# 4G_Module.net
KiCad netlist of a schematic drawn in Altium Designer
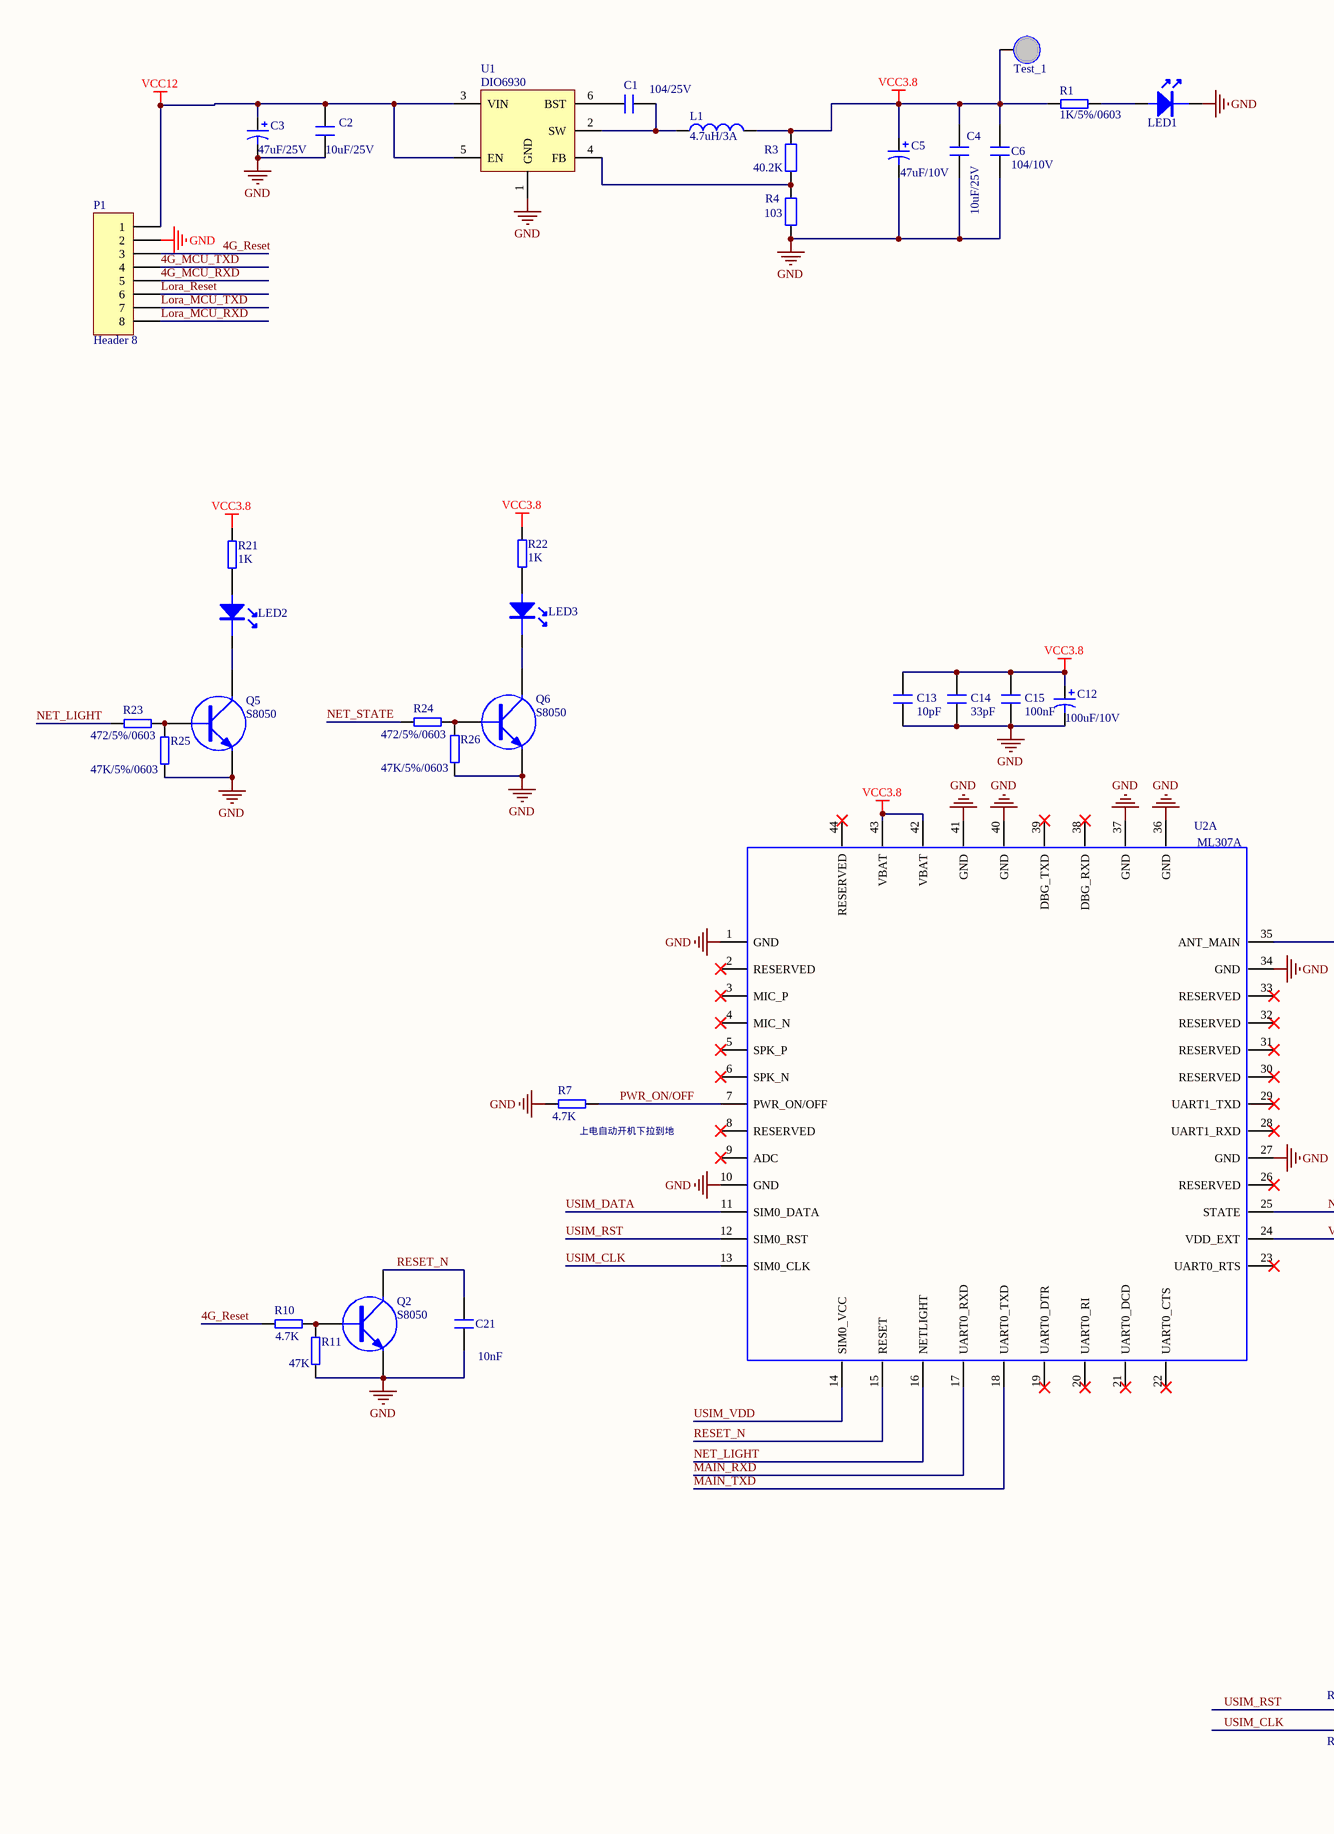
[diagram p0: 4G_Module.SchDoc, left]
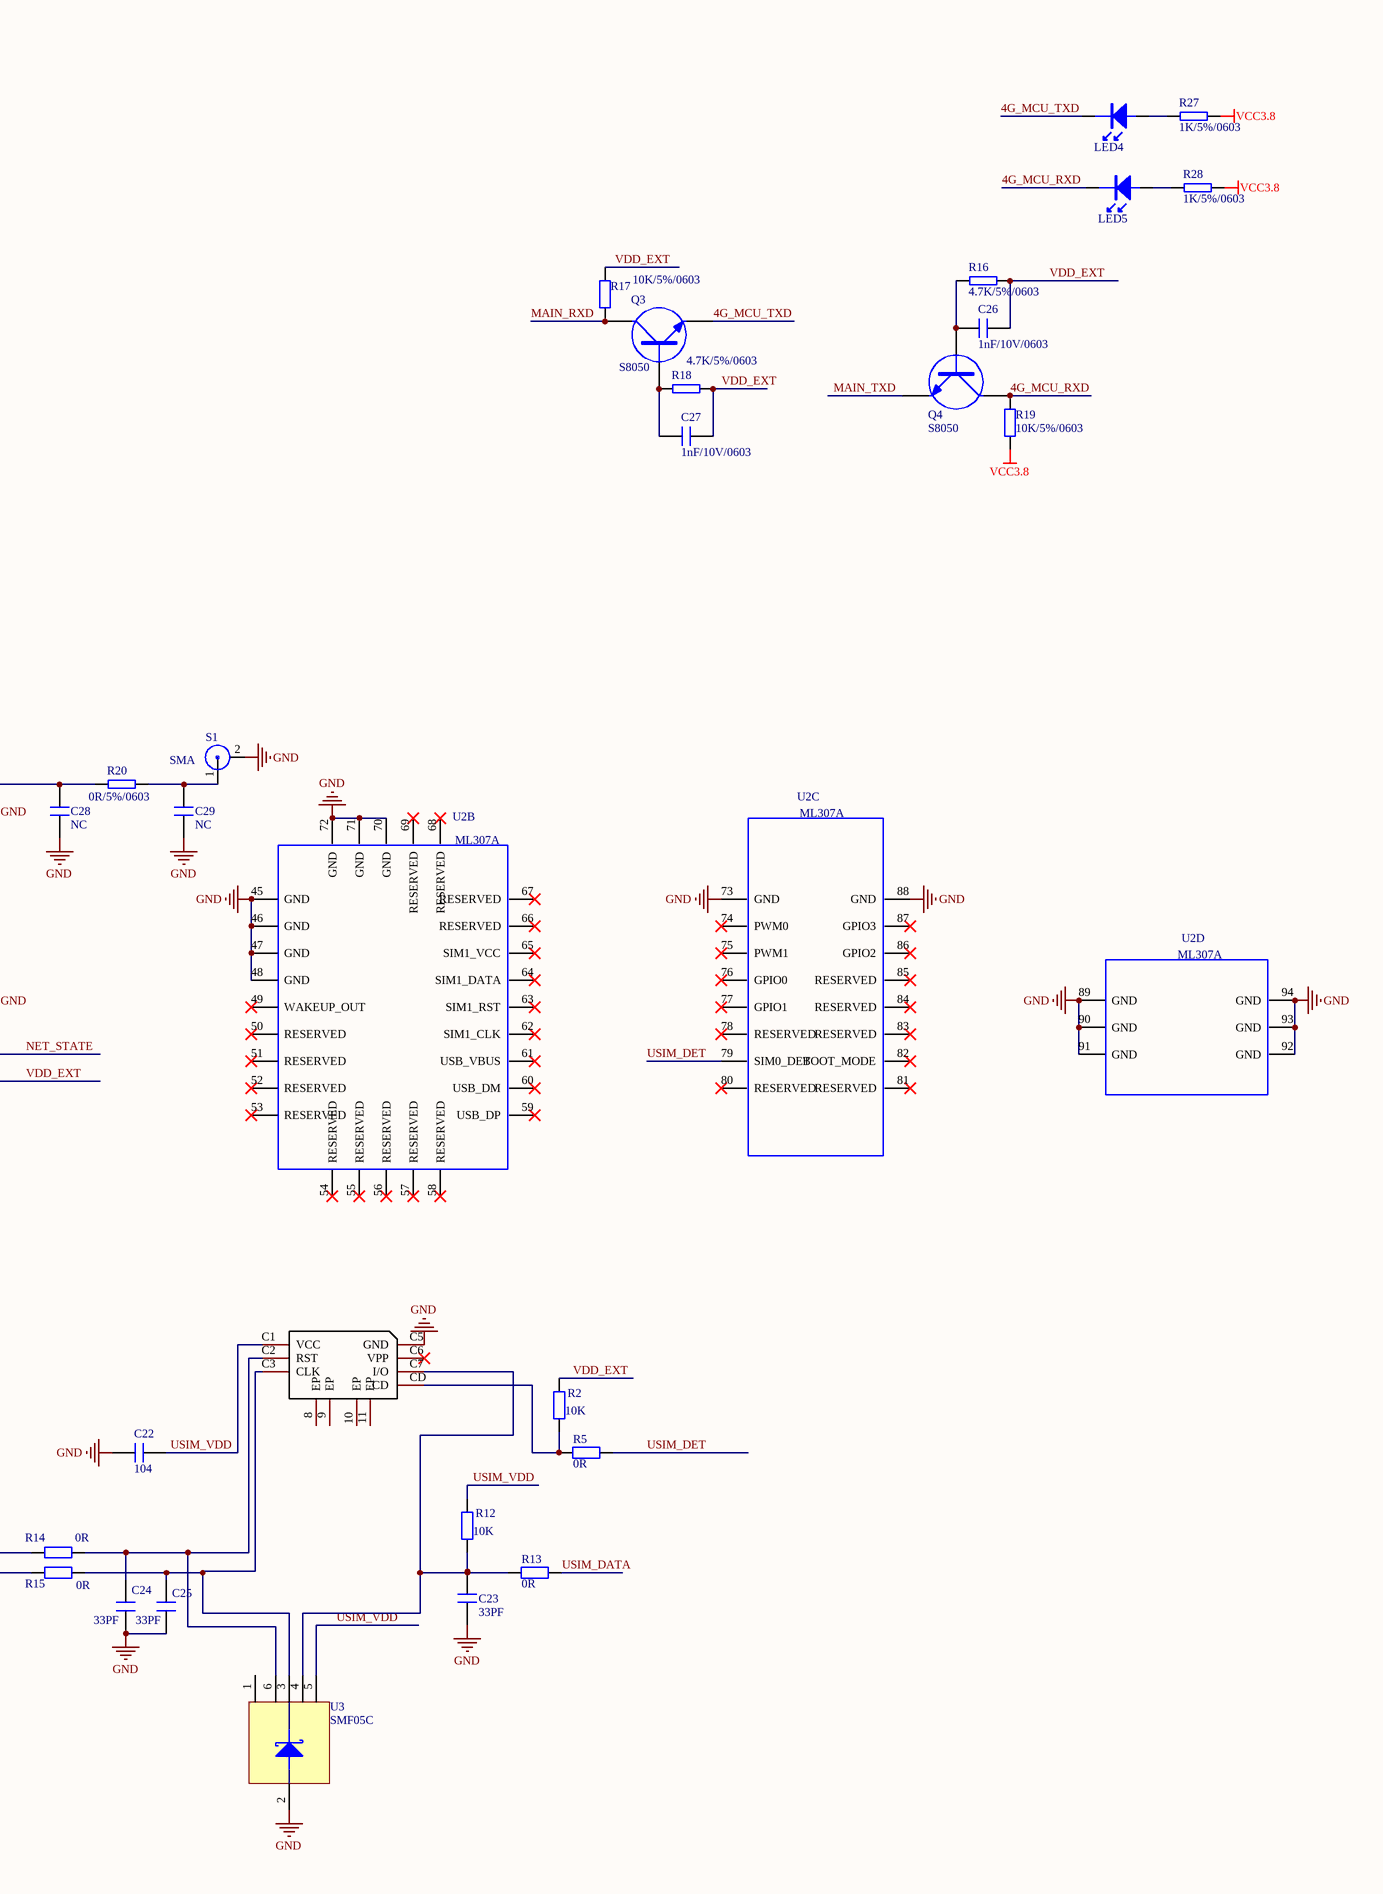
[diagram p1: 4G_Module.SchDoc, right]

(export (version "E")
  (design (tool "Eeschema 10.0.6"))
  (components
    (comp (ref "C1") (value "104/25V") (footprint "0603R") (libsource (lib "ES_Schematic") (part "CAP_1")))
    (comp (ref "C2") (value "10uF/25V") (footprint "0603R") (libsource (lib "ES_Schematic") (part "CAP")))
    (comp (ref "C3")
      (value "47uF/25V")
      (footprint "0805R")
      (description "Polarized Capacitor (Radial)")
      (fields (field (name "PUBLISHER") "Altium Limited"))
      (libsource (lib "Miscellaneous Devices") (part "Cap Pol1"))
    )
    (comp (ref "C4") (value "10uF/25V") (footprint "0603R") (libsource (lib "ES_Schematic") (part "CAP")))
    (comp (ref "C5")
      (value "47uF/10V")
      (footprint "0805R")
      (description "Polarized Capacitor (Radial)")
      (fields (field (name "PUBLISHER") "Altium Limited"))
      (libsource (lib "Miscellaneous Devices") (part "Cap Pol1"))
    )
    (comp (ref "C6") (value "104/10V") (footprint "0603R") (libsource (lib "ES_Schematic") (part "CAP_1")))
    (comp (ref "C12")
      (value "100uF/10V")
      (footprint "C1210")
      (description "Polarized Capacitor (Radial)")
      (fields (field (name "PUBLISHER") "Altium Limited"))
      (libsource (lib "Miscellaneous Devices") (part "Cap Pol1"))
    )
    (comp (ref "C13") (value "10pF") (footprint "0603R") (libsource (lib "ES_Schematic") (part "CAP_1")))
    (comp (ref "C14") (value "33pF") (footprint "0603R") (libsource (lib "ES_Schematic") (part "CAP_1")))
    (comp (ref "C15") (value "100nF") (footprint "0603R") (libsource (lib "ES_Schematic") (part "CAP_1")))
    (comp (ref "C21") (value "10nF") (footprint "0603R") (libsource (lib "ES_Schematic") (part "CAP_1")))
    (comp (ref "C22") (value "104") (footprint "0603R") (libsource (lib "ES_Schematic") (part "CAP")))
    (comp (ref "C23") (value "33PF") (footprint "0603R") (libsource (lib "ES_Schematic") (part "CAP")))
    (comp (ref "C24") (value "33PF") (footprint "0603R") (libsource (lib "ES_Schematic") (part "CAP")))
    (comp (ref "C25") (value "33PF") (footprint "0603R") (libsource (lib "ES_Schematic") (part "CAP")))
    (comp (ref "C26")
      (value "1nF/10V/0603")
      (footprint "0603R")
      (libsource (lib "ES_Schematic") (part "CAP"))
    )
    (comp (ref "C27")
      (value "1nF/10V/0603")
      (footprint "0603R")
      (libsource (lib "ES_Schematic") (part "CAP"))
    )
    (comp (ref "C28") (value "NC") (footprint "0603R") (libsource (lib "ES_Schematic") (part "CAP")))
    (comp (ref "C29") (value "NC") (footprint "0603R") (libsource (lib "ES_Schematic") (part "CAP")))
    (comp (ref "CARD1")
      (value "SMN-303")
      (footprint "Nano-SIM")
      (fields (field (name "MANUFACTURER") "XUNPU(讯普)"))
      (libsource (lib "altium-import") (part "root_0_SMN-303_"))
    )
    (comp (ref "L1")
      (value "4.7uH/3A")
      (footprint "CD54")
      (description "Inductor")
      (fields (field (name "PUBLISHER") "Altium Limited"))
      (libsource (lib "Miscellaneous Devices") (part "Inductor"))
    )
    (comp (ref "LED1") (value "LED") (footprint "0603LED") (libsource (lib "ES_Schematic") (part "LED")))
    (comp (ref "LED2") (value "LED") (footprint "0603LED") (libsource (lib "ES_Schematic") (part "LED")))
    (comp (ref "LED3") (value "LED") (footprint "0603LED") (libsource (lib "ES_Schematic") (part "LED")))
    (comp (ref "LED4") (value "LED") (footprint "0603LED") (libsource (lib "ES_Schematic") (part "LED")))
    (comp (ref "LED5") (value "LED") (footprint "0603LED") (libsource (lib "ES_Schematic") (part "LED")))
    (comp (ref "P1")
      (value "Header 8")
      (footprint "HDR1X8")
      (description "Header, 8-Pin")
      (fields (field (name "PUBLISHER") "Altium Limited"))
      (libsource (lib "Miscellaneous Connectors") (part "Header 8"))
    )
    (comp (ref "Q2") (value "S8050") (footprint "SOT-23") (libsource (lib "ES_Schematic") (part "NPN")))
    (comp (ref "Q3") (value "S8050") (footprint "SOT-23") (libsource (lib "ES_Schematic") (part "NPN")))
    (comp (ref "Q4") (value "S8050") (footprint "SOT-23") (libsource (lib "ES_Schematic") (part "NPN")))
    (comp (ref "Q5") (value "S8050") (footprint "SOT-23") (libsource (lib "ES_Schematic") (part "NPN")))
    (comp (ref "Q6") (value "S8050") (footprint "SOT-23") (libsource (lib "ES_Schematic") (part "NPN")))
    (comp (ref "R1") (value "1K/5%/0603") (footprint "0603R") (libsource (lib "ES_Schematic") (part "RES")))
    (comp (ref "R2")
      (value "10K")
      (footprint "0603R")
      (description "Resistor")
      (fields (field (name "PUBLISHER") "Altium Limited"))
      (libsource (lib "Miscellaneous Devices") (part "Res2"))
    )
    (comp (ref "R3")
      (value "40.2K")
      (footprint "0603R")
      (description "Resistor")
      (fields (field (name "PUBLISHER") "Altium Limited"))
      (libsource (lib "Miscellaneous Devices") (part "Res2"))
    )
    (comp (ref "R4")
      (value "103")
      (footprint "0603R")
      (description "Resistor")
      (fields (field (name "PUBLISHER") "Altium Limited"))
      (libsource (lib "Miscellaneous Devices") (part "Res2"))
    )
    (comp (ref "R5")
      (value "0R")
      (footprint "0603R")
      (description "Resistor")
      (fields (field (name "PUBLISHER") "Altium Limited"))
      (libsource (lib "") (part "Res2_1"))
    )
    (comp (ref "R7") (value "4.7K") (footprint "0603R") (libsource (lib "ES_Schematic") (part "RES")))
    (comp (ref "R10") (value "4.7K") (footprint "0603R") (libsource (lib "ES_Schematic") (part "RES")))
    (comp (ref "R11") (value "47K") (footprint "0603R") (libsource (lib "ES_Schematic") (part "RES")))
    (comp (ref "R12")
      (value "10K")
      (footprint "0603R")
      (description "Resistor")
      (fields (field (name "PUBLISHER") "Altium Limited"))
      (libsource (lib "Miscellaneous Devices") (part "Res2"))
    )
    (comp (ref "R13")
      (value "0R")
      (footprint "0603R")
      (description "Resistor")
      (fields (field (name "PUBLISHER") "Altium Limited"))
      (libsource (lib "") (part "Res2_1"))
    )
    (comp (ref "R14")
      (value "0R")
      (footprint "0603R")
      (description "Resistor")
      (fields (field (name "PUBLISHER") "Altium Limited"))
      (libsource (lib "") (part "Res2_1"))
    )
    (comp (ref "R15")
      (value "0R")
      (footprint "0603R")
      (description "Resistor")
      (fields (field (name "PUBLISHER") "Altium Limited"))
      (libsource (lib "") (part "Res2_1"))
    )
    (comp (ref "R16")
      (value "4.7K/5%/0603")
      (footprint "0603R")
      (libsource (lib "ES_Schematic") (part "RES"))
    )
    (comp (ref "R17")
      (value "10K/5%/0603")
      (footprint "0603R")
      (description "Resistor")
      (fields (field (name "PUBLISHER") "Altium Limited"))
      (libsource (lib "Miscellaneous Devices") (part "Res2"))
    )
    (comp (ref "R18")
      (value "4.7K/5%/0603")
      (footprint "0603R")
      (libsource (lib "ES_Schematic") (part "RES"))
    )
    (comp (ref "R19")
      (value "10K/5%/0603")
      (footprint "0603R")
      (description "Resistor")
      (fields (field (name "PUBLISHER") "Altium Limited"))
      (libsource (lib "Miscellaneous Devices") (part "Res2"))
    )
    (comp (ref "R20") (value "0R/5%/0603") (footprint "0603R") (libsource (lib "ES_Schematic") (part "RES")))
    (comp (ref "R21") (value "1K") (footprint "0603R") (libsource (lib "ES_Schematic") (part "RES")))
    (comp (ref "R22") (value "1K") (footprint "0603R") (libsource (lib "ES_Schematic") (part "RES")))
    (comp (ref "R23") (value "472/5%/0603") (footprint "0603R") (libsource (lib "ES_Schematic") (part "RES")))
    (comp (ref "R24") (value "472/5%/0603") (footprint "0603R") (libsource (lib "ES_Schematic") (part "RES")))
    (comp (ref "R25") (value "47K/5%/0603") (footprint "0603R") (libsource (lib "ES_Schematic") (part "RES")))
    (comp (ref "R26") (value "47K/5%/0603") (footprint "0603R") (libsource (lib "ES_Schematic") (part "RES")))
    (comp (ref "R27") (value "1K/5%/0603") (footprint "0603R") (libsource (lib "ES_Schematic") (part "RES")))
    (comp (ref "R28") (value "1K/5%/0603") (footprint "0603R") (libsource (lib "ES_Schematic") (part "RES")))
    (comp (ref "S1") (value "SMA") (footprint "RF1-00283天线座") (libsource (lib "ES_Schematic") (part "SMA")))
    (comp (ref "Test_1") (value "MARK") (footprint "MARK") (libsource (lib "others") (part "MARK")))
    (comp (ref "U1")
      (value "DIO6930")
      (footprint "SOT-23-6DBV")
      (libsource (lib "ES_Schematic") (part "BL8032"))
    )
    (comp (ref "U2") (value "ML307A") (footprint "ML307A") (libsource (lib "") (part "ML307A_3")))
    (comp (ref "U3") (value "SMF05C") (footprint "SC70-6L") (libsource (lib "ES_Schematic") (part "SMF05C")))
  )
  (nets
    (net (code "1") (name "/4G_MCU_RXD") (class "Default")
      (node (ref "LED5") (pin "2") (pinfunction "2_2") (pintype "passive"))
      (node (ref "P1") (pin "5") (pinfunction "5_5") (pintype "passive"))
      (node (ref "Q4") (pin "3") (pinfunction "C_3") (pintype "passive"))
      (node (ref "R19") (pin "1") (pinfunction "1_1") (pintype "passive"))
    )
    (net (code "2") (name "/4G_MCU_TXD") (class "Default")
      (node (ref "LED4") (pin "2") (pinfunction "2_2") (pintype "passive"))
      (node (ref "P1") (pin "4") (pinfunction "4_4") (pintype "passive"))
      (node (ref "Q3") (pin "2") (pinfunction "E_2") (pintype "passive"))
    )
    (net (code "3") (name "/4G_Reset") (class "Default")
      (node (ref "P1") (pin "3") (pinfunction "3_3") (pintype "passive"))
      (node (ref "R10") (pin "1") (pinfunction "1_1") (pintype "passive"))
    )
    (net (code "4") (name "/Lora_MCU_RXD") (class "Default")
      (node (ref "P1") (pin "8") (pinfunction "8_8") (pintype "passive"))
    )
    (net (code "5") (name "/Lora_MCU_TXD") (class "Default")
      (node (ref "P1") (pin "7") (pinfunction "7_7") (pintype "passive"))
    )
    (net (code "6") (name "/Lora_Reset") (class "Default")
      (node (ref "P1") (pin "6") (pinfunction "6_6") (pintype "passive"))
    )
    (net (code "7") (name "/MAIN_RXD") (class "Default")
      (node (ref "Q3") (pin "3") (pinfunction "C_3") (pintype "passive"))
      (node (ref "R17") (pin "2") (pinfunction "2_2") (pintype "passive"))
      (node (ref "U2") (pin "17") (pinfunction "UART0_RXD_17") (pintype "passive"))
    )
    (net (code "8") (name "/MAIN_TXD") (class "Default")
      (node (ref "Q4") (pin "2") (pinfunction "E_2") (pintype "passive"))
      (node (ref "U2") (pin "18") (pinfunction "UART0_TXD_18") (pintype "passive"))
    )
    (net (code "9") (name "/NET_LIGHT") (class "Default")
      (node (ref "R23") (pin "1") (pinfunction "1_1") (pintype "passive"))
      (node (ref "U2") (pin "16") (pinfunction "NETLIGHT_16") (pintype "passive"))
    )
    (net (code "10") (name "/NET_STATE") (class "Default")
      (node (ref "R24") (pin "1") (pinfunction "1_1") (pintype "passive"))
      (node (ref "U2") (pin "25") (pinfunction "STATE_25") (pintype "passive"))
    )
    (net (code "11") (name "/PWR_ON{slash}OFF") (class "Default")
      (node (ref "R7") (pin "1") (pinfunction "1_1") (pintype "passive"))
      (node (ref "U2") (pin "7") (pinfunction "PWR_ON/OFF_7") (pintype "passive"))
    )
    (net (code "12") (name "/RESET_N") (class "Default")
      (node (ref "C21") (pin "2") (pinfunction "2_2") (pintype "passive"))
      (node (ref "Q2") (pin "3") (pinfunction "C_3") (pintype "passive"))
      (node (ref "U2") (pin "15") (pinfunction "RESET_15") (pintype "passive"))
    )
    (net (code "13") (name "/USIM_CLK") (class "Default")
      (node (ref "R15") (pin "2") (pinfunction "2_2") (pintype "passive"))
      (node (ref "U2") (pin "13") (pinfunction "SIM0_CLK_13") (pintype "passive"))
    )
    (net (code "14") (name "/USIM_DATA") (class "Default")
      (node (ref "R13") (pin "1") (pinfunction "1_1") (pintype "passive"))
      (node (ref "U2") (pin "11") (pinfunction "SIM0_DATA_11") (pintype "passive"))
    )
    (net (code "15") (name "/USIM_DET") (class "Default")
      (node (ref "R5") (pin "1") (pinfunction "1_1") (pintype "passive"))
      (node (ref "U2") (pin "79") (pinfunction "SIM0_DET_79") (pintype "passive"))
    )
    (net (code "16") (name "/USIM_RST") (class "Default")
      (node (ref "R14") (pin "2") (pinfunction "2_2") (pintype "passive"))
      (node (ref "U2") (pin "12") (pinfunction "SIM0_RST_12") (pintype "passive"))
    )
    (net (code "17") (name "/USIM_VDD") (class "Default")
      (node (ref "C22") (pin "2") (pinfunction "2_2") (pintype "passive"))
      (node (ref "CARD1") (pin "C1") (pinfunction "VCC_C1") (pintype "passive"))
      (node (ref "R12") (pin "1") (pinfunction "1_1") (pintype "passive"))
      (node (ref "U2") (pin "14") (pinfunction "SIM0_VCC_14") (pintype "passive"))
      (node (ref "U3") (pin "5") (pintype "passive"))
    )
    (net (code "18") (name "/VDD_EXT") (class "Default")
      (node (ref "C26") (pin "2") (pinfunction "2_2") (pintype "passive"))
      (node (ref "C27") (pin "2") (pinfunction "2_2") (pintype "passive"))
      (node (ref "R16") (pin "2") (pinfunction "2_2") (pintype "passive"))
      (node (ref "R17") (pin "1") (pinfunction "1_1") (pintype "passive"))
      (node (ref "R18") (pin "2") (pinfunction "2_2") (pintype "passive"))
      (node (ref "R2") (pin "1") (pinfunction "1_1") (pintype "passive"))
      (node (ref "U2") (pin "24") (pinfunction "VDD_EXT_24") (pintype "passive"))
    )
    (net (code "19") (name "GND") (class "Default")
      (node (ref "C12") (pin "2") (pinfunction "2_2") (pintype "passive"))
      (node (ref "C13") (pin "2") (pinfunction "2_2") (pintype "passive"))
      (node (ref "C14") (pin "2") (pinfunction "2_2") (pintype "passive"))
      (node (ref "C15") (pin "2") (pinfunction "2_2") (pintype "passive"))
      (node (ref "C2") (pin "1") (pinfunction "1_1") (pintype "passive"))
      (node (ref "C21") (pin "1") (pinfunction "1_1") (pintype "passive"))
      (node (ref "C22") (pin "1") (pinfunction "1_1") (pintype "passive"))
      (node (ref "C23") (pin "1") (pinfunction "1_1") (pintype "passive"))
      (node (ref "C24") (pin "2") (pinfunction "2_2") (pintype "passive"))
      (node (ref "C25") (pin "2") (pinfunction "2_2") (pintype "passive"))
      (node (ref "C28") (pin "1") (pinfunction "1_1") (pintype "passive"))
      (node (ref "C29") (pin "1") (pinfunction "1_1") (pintype "passive"))
      (node (ref "C3") (pin "2") (pinfunction "2_2") (pintype "passive"))
      (node (ref "C4") (pin "1") (pinfunction "1_1") (pintype "passive"))
      (node (ref "C5") (pin "2") (pinfunction "2_2") (pintype "passive"))
      (node (ref "C6") (pin "1") (pinfunction "1_1") (pintype "passive"))
      (node (ref "CARD1") (pin "C5") (pinfunction "GND_C5") (pintype "passive"))
      (node (ref "LED1") (pin "2") (pinfunction "2_2") (pintype "passive"))
      (node (ref "P1") (pin "2") (pinfunction "2_2") (pintype "passive"))
      (node (ref "Q2") (pin "2") (pinfunction "E_2") (pintype "passive"))
      (node (ref "Q5") (pin "2") (pinfunction "E_2") (pintype "passive"))
      (node (ref "Q6") (pin "2") (pinfunction "E_2") (pintype "passive"))
      (node (ref "R11") (pin "2") (pinfunction "2_2") (pintype "passive"))
      (node (ref "R25") (pin "2") (pinfunction "2_2") (pintype "passive"))
      (node (ref "R26") (pin "2") (pinfunction "2_2") (pintype "passive"))
      (node (ref "R4") (pin "2") (pinfunction "2_2") (pintype "passive"))
      (node (ref "R7") (pin "2") (pinfunction "2_2") (pintype "passive"))
      (node (ref "S1") (pin "2") (pinfunction "2_2") (pintype "passive"))
      (node (ref "U1") (pin "1") (pinfunction "GND_1") (pintype "passive"))
      (node (ref "U2") (pin "1") (pinfunction "GND_1") (pintype "passive"))
      (node (ref "U2") (pin "10") (pinfunction "GND_10") (pintype "passive"))
      (node (ref "U2") (pin "27") (pinfunction "GND_27") (pintype "passive"))
      (node (ref "U2") (pin "34") (pinfunction "GND_34") (pintype "passive"))
      (node (ref "U2") (pin "36") (pinfunction "GND_36") (pintype "passive"))
      (node (ref "U2") (pin "37") (pinfunction "GND_37") (pintype "passive"))
      (node (ref "U2") (pin "40") (pinfunction "GND_40") (pintype "passive"))
      (node (ref "U2") (pin "41") (pinfunction "GND_41") (pintype "passive"))
      (node (ref "U2") (pin "45") (pinfunction "GND_45") (pintype "passive"))
      (node (ref "U2") (pin "46") (pinfunction "GND_46") (pintype "passive"))
      (node (ref "U2") (pin "47") (pinfunction "GND_47") (pintype "passive"))
      (node (ref "U2") (pin "48") (pinfunction "GND_48") (pintype "passive"))
      (node (ref "U2") (pin "70") (pinfunction "GND_70") (pintype "passive"))
      (node (ref "U2") (pin "71") (pinfunction "GND_71") (pintype "passive"))
      (node (ref "U2") (pin "72") (pinfunction "GND_72") (pintype "passive"))
      (node (ref "U2") (pin "73") (pinfunction "GND_73") (pintype "passive"))
      (node (ref "U2") (pin "88") (pinfunction "GND_88") (pintype "passive"))
      (node (ref "U2") (pin "89") (pinfunction "GND_89") (pintype "passive"))
      (node (ref "U2") (pin "90") (pinfunction "GND_90") (pintype "passive"))
      (node (ref "U2") (pin "91") (pinfunction "GND_91") (pintype "passive"))
      (node (ref "U2") (pin "92") (pinfunction "GND_92") (pintype "passive"))
      (node (ref "U2") (pin "93") (pinfunction "GND_93") (pintype "passive"))
      (node (ref "U2") (pin "94") (pinfunction "GND_94") (pintype "passive"))
      (node (ref "U3") (pin "2") (pintype "passive"))
    )
    (net (code "20") (name "Net-(C29-Pad2)") (class "Default")
      (node (ref "C29") (pin "2") (pinfunction "2_2") (pintype "passive"))
      (node (ref "R20") (pin "2") (pinfunction "2_2") (pintype "passive"))
      (node (ref "S1") (pin "1") (pinfunction "1_1") (pintype "passive"))
    )
    (net (code "21") (name "Net-(CARD1-CLK)") (class "Default")
      (node (ref "C25") (pin "1") (pinfunction "1_1") (pintype "passive"))
      (node (ref "CARD1") (pin "C3") (pinfunction "CLK_C3") (pintype "passive"))
      (node (ref "R15") (pin "1") (pinfunction "1_1") (pintype "passive"))
      (node (ref "U3") (pin "3") (pintype "passive"))
    )
    (net (code "22") (name "Net-(CARD1-I{slash}O)") (class "Default")
      (node (ref "C23") (pin "2") (pinfunction "2_2") (pintype "passive"))
      (node (ref "CARD1") (pin "C7") (pinfunction "I/O_C7") (pintype "passive"))
      (node (ref "R12") (pin "2") (pinfunction "2_2") (pintype "passive"))
      (node (ref "R13") (pin "2") (pinfunction "2_2") (pintype "passive"))
      (node (ref "U3") (pin "4") (pintype "passive"))
    )
    (net (code "23") (name "Net-(CARD1-PadCD)") (class "Default")
      (node (ref "CARD1") (pin "CD") (pinfunction "CD_CD") (pintype "passive"))
      (node (ref "R2") (pin "2") (pinfunction "2_2") (pintype "passive"))
      (node (ref "R5") (pin "2") (pinfunction "2_2") (pintype "passive"))
    )
    (net (code "24") (name "Net-(CARD1-RST)") (class "Default")
      (node (ref "C24") (pin "1") (pinfunction "1_1") (pintype "passive"))
      (node (ref "CARD1") (pin "C2") (pinfunction "RST_C2") (pintype "passive"))
      (node (ref "R14") (pin "1") (pinfunction "1_1") (pintype "passive"))
      (node (ref "U3") (pin "6") (pintype "passive"))
    )
    (net (code "25") (name "Net-(LED1-Pad1)") (class "Default")
      (node (ref "LED1") (pin "1") (pinfunction "1_1") (pintype "passive"))
      (node (ref "R1") (pin "2") (pinfunction "2_2") (pintype "passive"))
    )
    (net (code "26") (name "Net-(LED2-Pad1)") (class "Default")
      (node (ref "LED2") (pin "1") (pinfunction "1_1") (pintype "passive"))
      (node (ref "R21") (pin "1") (pinfunction "1_1") (pintype "passive"))
    )
    (net (code "27") (name "Net-(LED3-Pad1)") (class "Default")
      (node (ref "LED3") (pin "1") (pinfunction "1_1") (pintype "passive"))
      (node (ref "R22") (pin "1") (pinfunction "1_1") (pintype "passive"))
    )
    (net (code "28") (name "Net-(LED4-Pad1)") (class "Default")
      (node (ref "LED4") (pin "1") (pinfunction "1_1") (pintype "passive"))
      (node (ref "R27") (pin "2") (pinfunction "2_2") (pintype "passive"))
    )
    (net (code "29") (name "Net-(LED5-Pad1)") (class "Default")
      (node (ref "LED5") (pin "1") (pinfunction "1_1") (pintype "passive"))
      (node (ref "R28") (pin "2") (pinfunction "2_2") (pintype "passive"))
    )
    (net (code "30") (name "Net-(Q2-B)") (class "Default")
      (node (ref "Q2") (pin "1") (pinfunction "B_1") (pintype "passive"))
      (node (ref "R10") (pin "2") (pinfunction "2_2") (pintype "passive"))
      (node (ref "R11") (pin "1") (pinfunction "1_1") (pintype "passive"))
    )
    (net (code "31") (name "Net-(Q3-B)") (class "Default")
      (node (ref "C27") (pin "1") (pinfunction "1_1") (pintype "passive"))
      (node (ref "Q3") (pin "1") (pinfunction "B_1") (pintype "passive"))
      (node (ref "R18") (pin "1") (pinfunction "1_1") (pintype "passive"))
    )
    (net (code "32") (name "Net-(Q4-B)") (class "Default")
      (node (ref "C26") (pin "1") (pinfunction "1_1") (pintype "passive"))
      (node (ref "Q4") (pin "1") (pinfunction "B_1") (pintype "passive"))
      (node (ref "R16") (pin "1") (pinfunction "1_1") (pintype "passive"))
    )
    (net (code "33") (name "Net-(Q5-B)") (class "Default")
      (node (ref "Q5") (pin "1") (pinfunction "B_1") (pintype "passive"))
      (node (ref "R23") (pin "2") (pinfunction "2_2") (pintype "passive"))
      (node (ref "R25") (pin "1") (pinfunction "1_1") (pintype "passive"))
    )
    (net (code "34") (name "Net-(Q5-C)") (class "Default")
      (node (ref "LED2") (pin "2") (pinfunction "2_2") (pintype "passive"))
      (node (ref "Q5") (pin "3") (pinfunction "C_3") (pintype "passive"))
    )
    (net (code "35") (name "Net-(Q6-B)") (class "Default")
      (node (ref "Q6") (pin "1") (pinfunction "B_1") (pintype "passive"))
      (node (ref "R24") (pin "2") (pinfunction "2_2") (pintype "passive"))
      (node (ref "R26") (pin "1") (pinfunction "1_1") (pintype "passive"))
    )
    (net (code "36") (name "Net-(Q6-C)") (class "Default")
      (node (ref "LED3") (pin "2") (pinfunction "2_2") (pintype "passive"))
      (node (ref "Q6") (pin "3") (pinfunction "C_3") (pintype "passive"))
    )
    (net (code "37") (name "Net-(U1-BST)") (class "Default")
      (node (ref "C1") (pin "2") (pinfunction "2_2") (pintype "passive"))
      (node (ref "U1") (pin "6") (pinfunction "BST_6") (pintype "passive"))
    )
    (net (code "38") (name "Net-(U1-FB)") (class "Default")
      (node (ref "R3") (pin "2") (pinfunction "2_2") (pintype "passive"))
      (node (ref "R4") (pin "1") (pinfunction "1_1") (pintype "passive"))
      (node (ref "U1") (pin "4") (pinfunction "FB_4") (pintype "passive"))
    )
    (net (code "39") (name "Net-(U1-SW)") (class "Default")
      (node (ref "C1") (pin "1") (pinfunction "1_1") (pintype "passive"))
      (node (ref "L1") (pin "1") (pinfunction "1_1") (pintype "passive"))
      (node (ref "U1") (pin "2") (pinfunction "SW_2") (pintype "passive"))
    )
    (net (code "40") (name "Net-(U2A-ANT_MAIN)") (class "Default")
      (node (ref "C28") (pin "2") (pinfunction "2_2") (pintype "passive"))
      (node (ref "R20") (pin "1") (pinfunction "1_1") (pintype "passive"))
      (node (ref "U2") (pin "35") (pinfunction "ANT_MAIN_35") (pintype "passive"))
    )
    (net (code "41") (name "VCC3.8") (class "Default")
      (node (ref "C12") (pin "1") (pinfunction "1_1") (pintype "passive"))
      (node (ref "C13") (pin "1") (pinfunction "1_1") (pintype "passive"))
      (node (ref "C14") (pin "1") (pinfunction "1_1") (pintype "passive"))
      (node (ref "C15") (pin "1") (pinfunction "1_1") (pintype "passive"))
      (node (ref "C4") (pin "2") (pinfunction "2_2") (pintype "passive"))
      (node (ref "C5") (pin "1") (pinfunction "1_1") (pintype "passive"))
      (node (ref "C6") (pin "2") (pinfunction "2_2") (pintype "passive"))
      (node (ref "L1") (pin "2") (pinfunction "2_2") (pintype "passive"))
      (node (ref "R1") (pin "1") (pinfunction "1_1") (pintype "passive"))
      (node (ref "R19") (pin "2") (pinfunction "2_2") (pintype "passive"))
      (node (ref "R21") (pin "2") (pinfunction "2_2") (pintype "passive"))
      (node (ref "R22") (pin "2") (pinfunction "2_2") (pintype "passive"))
      (node (ref "R27") (pin "1") (pinfunction "1_1") (pintype "passive"))
      (node (ref "R28") (pin "1") (pinfunction "1_1") (pintype "passive"))
      (node (ref "R3") (pin "1") (pinfunction "1_1") (pintype "passive"))
      (node (ref "Test_1") (pin "1") (pinfunction "1_1") (pintype "passive"))
      (node (ref "U2") (pin "42") (pinfunction "VBAT_42") (pintype "passive"))
      (node (ref "U2") (pin "43") (pinfunction "VBAT_43") (pintype "passive"))
    )
    (net (code "42") (name "VCC12") (class "Default")
      (node (ref "C2") (pin "2") (pinfunction "2_2") (pintype "passive"))
      (node (ref "C3") (pin "1") (pinfunction "1_1") (pintype "passive"))
      (node (ref "P1") (pin "1") (pinfunction "1_1") (pintype "passive"))
      (node (ref "U1") (pin "3") (pinfunction "VIN_3") (pintype "passive"))
      (node (ref "U1") (pin "5") (pinfunction "EN_5") (pintype "passive"))
    )
    (net (code "43") (name "unconnected-(CARD1-EP-Pad8)") (class "Default")
      (node (ref "CARD1") (pin "8") (pinfunction "EP_8") (pintype "passive"))
    )
    (net (code "44") (name "unconnected-(CARD1-EP-Pad9)") (class "Default")
      (node (ref "CARD1") (pin "9") (pinfunction "EP_9") (pintype "passive"))
    )
    (net (code "45") (name "unconnected-(CARD1-EP-Pad10)") (class "Default")
      (node (ref "CARD1") (pin "10") (pinfunction "EP_10") (pintype "passive"))
    )
    (net (code "46") (name "unconnected-(CARD1-EP-Pad11)") (class "Default")
      (node (ref "CARD1") (pin "11") (pinfunction "EP_11") (pintype "passive"))
    )
    (net (code "47") (name "unconnected-(CARD1-VPP-PadC6)") (class "Default")
      (node (ref "CARD1") (pin "C6") (pinfunction "VPP_C6") (pintype "passive+no_connect"))
    )
    (net (code "48") (name "unconnected-(U2A-ADC-Pad9)") (class "Default")
      (node (ref "U2") (pin "9") (pinfunction "ADC_9") (pintype "passive+no_connect"))
    )
    (net (code "49") (name "unconnected-(U2A-DBG_RXD-Pad38)") (class "Default")
      (node (ref "U2") (pin "38") (pinfunction "DBG_RXD_38") (pintype "passive+no_connect"))
    )
    (net (code "50") (name "unconnected-(U2A-DBG_TXD-Pad39)") (class "Default")
      (node (ref "U2") (pin "39") (pinfunction "DBG_TXD_39") (pintype "passive+no_connect"))
    )
    (net (code "51") (name "unconnected-(U2A-MIC_N-Pad4)") (class "Default")
      (node (ref "U2") (pin "4") (pinfunction "MIC_N_4") (pintype "passive+no_connect"))
    )
    (net (code "52") (name "unconnected-(U2A-MIC_P-Pad3)") (class "Default")
      (node (ref "U2") (pin "3") (pinfunction "MIC_P_3") (pintype "passive+no_connect"))
    )
    (net (code "53") (name "unconnected-(U2A-RESERVED-Pad2)") (class "Default")
      (node (ref "U2") (pin "2") (pinfunction "RESERVED_2") (pintype "passive+no_connect"))
    )
    (net (code "54") (name "unconnected-(U2A-RESERVED-Pad8)") (class "Default")
      (node (ref "U2") (pin "8") (pinfunction "RESERVED_8") (pintype "passive+no_connect"))
    )
    (net (code "55") (name "unconnected-(U2A-RESERVED-Pad26)") (class "Default")
      (node (ref "U2") (pin "26") (pinfunction "RESERVED_26") (pintype "passive+no_connect"))
    )
    (net (code "56") (name "unconnected-(U2A-RESERVED-Pad30)") (class "Default")
      (node (ref "U2") (pin "30") (pinfunction "RESERVED_30") (pintype "passive+no_connect"))
    )
    (net (code "57") (name "unconnected-(U2A-RESERVED-Pad31)") (class "Default")
      (node (ref "U2") (pin "31") (pinfunction "RESERVED_31") (pintype "passive+no_connect"))
    )
    (net (code "58") (name "unconnected-(U2A-RESERVED-Pad32)") (class "Default")
      (node (ref "U2") (pin "32") (pinfunction "RESERVED_32") (pintype "passive+no_connect"))
    )
    (net (code "59") (name "unconnected-(U2A-RESERVED-Pad33)") (class "Default")
      (node (ref "U2") (pin "33") (pinfunction "RESERVED_33") (pintype "passive+no_connect"))
    )
    (net (code "60") (name "unconnected-(U2A-RESERVED-Pad44)") (class "Default")
      (node (ref "U2") (pin "44") (pinfunction "RESERVED_44") (pintype "passive+no_connect"))
    )
    (net (code "61") (name "unconnected-(U2A-SPK_N-Pad6)") (class "Default")
      (node (ref "U2") (pin "6") (pinfunction "SPK_N_6") (pintype "passive+no_connect"))
    )
    (net (code "62") (name "unconnected-(U2A-SPK_P-Pad5)") (class "Default")
      (node (ref "U2") (pin "5") (pinfunction "SPK_P_5") (pintype "passive+no_connect"))
    )
    (net (code "63") (name "unconnected-(U2A-UART0_CTS-Pad22)") (class "Default")
      (node (ref "U2") (pin "22") (pinfunction "UART0_CTS_22") (pintype "passive+no_connect"))
    )
    (net (code "64") (name "unconnected-(U2A-UART0_DCD-Pad21)") (class "Default")
      (node (ref "U2") (pin "21") (pinfunction "UART0_DCD_21") (pintype "passive+no_connect"))
    )
    (net (code "65") (name "unconnected-(U2A-UART0_DTR-Pad19)") (class "Default")
      (node (ref "U2") (pin "19") (pinfunction "UART0_DTR_19") (pintype "passive+no_connect"))
    )
    (net (code "66") (name "unconnected-(U2A-UART0_RI-Pad20)") (class "Default")
      (node (ref "U2") (pin "20") (pinfunction "UART0_RI_20") (pintype "passive+no_connect"))
    )
    (net (code "67") (name "unconnected-(U2A-UART0_RTS-Pad23)") (class "Default")
      (node (ref "U2") (pin "23") (pinfunction "UART0_RTS_23") (pintype "passive+no_connect"))
    )
    (net (code "68") (name "unconnected-(U2A-UART1_RXD-Pad28)") (class "Default")
      (node (ref "U2") (pin "28") (pinfunction "UART1_RXD_28") (pintype "passive+no_connect"))
    )
    (net (code "69") (name "unconnected-(U2A-UART1_TXD-Pad29)") (class "Default")
      (node (ref "U2") (pin "29") (pinfunction "UART1_TXD_29") (pintype "passive+no_connect"))
    )
    (net (code "70") (name "unconnected-(U2B-RESERVED-Pad50)") (class "Default")
      (node (ref "U2") (pin "50") (pinfunction "RESERVED_50") (pintype "passive+no_connect"))
    )
    (net (code "71") (name "unconnected-(U2B-RESERVED-Pad51)") (class "Default")
      (node (ref "U2") (pin "51") (pinfunction "RESERVED_51") (pintype "passive+no_connect"))
    )
    (net (code "72") (name "unconnected-(U2B-RESERVED-Pad52)") (class "Default")
      (node (ref "U2") (pin "52") (pinfunction "RESERVED_52") (pintype "passive+no_connect"))
    )
    (net (code "73") (name "unconnected-(U2B-RESERVED-Pad53)") (class "Default")
      (node (ref "U2") (pin "53") (pinfunction "RESERVED_53") (pintype "passive+no_connect"))
    )
    (net (code "74") (name "unconnected-(U2B-RESERVED-Pad54)") (class "Default")
      (node (ref "U2") (pin "54") (pinfunction "RESERVED_54") (pintype "passive+no_connect"))
    )
    (net (code "75") (name "unconnected-(U2B-RESERVED-Pad55)") (class "Default")
      (node (ref "U2") (pin "55") (pinfunction "RESERVED_55") (pintype "passive+no_connect"))
    )
    (net (code "76") (name "unconnected-(U2B-RESERVED-Pad56)") (class "Default")
      (node (ref "U2") (pin "56") (pinfunction "RESERVED_56") (pintype "passive+no_connect"))
    )
    (net (code "77") (name "unconnected-(U2B-RESERVED-Pad57)") (class "Default")
      (node (ref "U2") (pin "57") (pinfunction "RESERVED_57") (pintype "passive+no_connect"))
    )
    (net (code "78") (name "unconnected-(U2B-RESERVED-Pad58)") (class "Default")
      (node (ref "U2") (pin "58") (pinfunction "RESERVED_58") (pintype "passive+no_connect"))
    )
    (net (code "79") (name "unconnected-(U2B-RESERVED-Pad66)") (class "Default")
      (node (ref "U2") (pin "66") (pinfunction "RESERVED_66") (pintype "passive+no_connect"))
    )
    (net (code "80") (name "unconnected-(U2B-RESERVED-Pad67)") (class "Default")
      (node (ref "U2") (pin "67") (pinfunction "RESERVED_67") (pintype "passive+no_connect"))
    )
    (net (code "81") (name "unconnected-(U2B-RESERVED-Pad68)") (class "Default")
      (node (ref "U2") (pin "68") (pinfunction "RESERVED_68") (pintype "passive+no_connect"))
    )
    (net (code "82") (name "unconnected-(U2B-RESERVED-Pad69)") (class "Default")
      (node (ref "U2") (pin "69") (pinfunction "RESERVED_69") (pintype "passive+no_connect"))
    )
    (net (code "83") (name "unconnected-(U2B-SIM1_CLK-Pad62)") (class "Default")
      (node (ref "U2") (pin "62") (pinfunction "SIM1_CLK_62") (pintype "passive+no_connect"))
    )
    (net (code "84") (name "unconnected-(U2B-SIM1_DATA-Pad64)") (class "Default")
      (node (ref "U2") (pin "64") (pinfunction "SIM1_DATA_64") (pintype "passive+no_connect"))
    )
    (net (code "85") (name "unconnected-(U2B-SIM1_RST-Pad63)") (class "Default")
      (node (ref "U2") (pin "63") (pinfunction "SIM1_RST_63") (pintype "passive+no_connect"))
    )
    (net (code "86") (name "unconnected-(U2B-SIM1_VCC-Pad65)") (class "Default")
      (node (ref "U2") (pin "65") (pinfunction "SIM1_VCC_65") (pintype "passive+no_connect"))
    )
    (net (code "87") (name "unconnected-(U2B-USB_DM-Pad60)") (class "Default")
      (node (ref "U2") (pin "60") (pinfunction "USB_DM_60") (pintype "passive+no_connect"))
    )
    (net (code "88") (name "unconnected-(U2B-USB_DP-Pad59)") (class "Default")
      (node (ref "U2") (pin "59") (pinfunction "USB_DP_59") (pintype "passive+no_connect"))
    )
    (net (code "89") (name "unconnected-(U2B-USB_VBUS-Pad61)") (class "Default")
      (node (ref "U2") (pin "61") (pinfunction "USB_VBUS_61") (pintype "passive+no_connect"))
    )
    (net (code "90") (name "unconnected-(U2B-WAKEUP_OUT-Pad49)") (class "Default")
      (node (ref "U2") (pin "49") (pinfunction "WAKEUP_OUT_49") (pintype "passive+no_connect"))
    )
    (net (code "91") (name "unconnected-(U2C-BOOT_MODE-Pad82)") (class "Default")
      (node (ref "U2") (pin "82") (pinfunction "BOOT_MODE_82") (pintype "passive+no_connect"))
    )
    (net (code "92") (name "unconnected-(U2C-GPIO0-Pad76)") (class "Default")
      (node (ref "U2") (pin "76") (pinfunction "GPIO0_76") (pintype "passive+no_connect"))
    )
    (net (code "93") (name "unconnected-(U2C-GPIO1-Pad77)") (class "Default")
      (node (ref "U2") (pin "77") (pinfunction "GPIO1_77") (pintype "passive+no_connect"))
    )
    (net (code "94") (name "unconnected-(U2C-GPIO2-Pad86)") (class "Default")
      (node (ref "U2") (pin "86") (pinfunction "GPIO2_86") (pintype "passive+no_connect"))
    )
    (net (code "95") (name "unconnected-(U2C-GPIO3-Pad87)") (class "Default")
      (node (ref "U2") (pin "87") (pinfunction "GPIO3_87") (pintype "passive+no_connect"))
    )
    (net (code "96") (name "unconnected-(U2C-PWM0-Pad74)") (class "Default")
      (node (ref "U2") (pin "74") (pinfunction "PWM0_74") (pintype "passive+no_connect"))
    )
    (net (code "97") (name "unconnected-(U2C-PWM1-Pad75)") (class "Default")
      (node (ref "U2") (pin "75") (pinfunction "PWM1_75") (pintype "passive+no_connect"))
    )
    (net (code "98") (name "unconnected-(U2C-RESERVED-Pad78)") (class "Default")
      (node (ref "U2") (pin "78") (pinfunction "RESERVED_78") (pintype "passive+no_connect"))
    )
    (net (code "99") (name "unconnected-(U2C-RESERVED-Pad80)") (class "Default")
      (node (ref "U2") (pin "80") (pinfunction "RESERVED_80") (pintype "passive+no_connect"))
    )
    (net (code "100") (name "unconnected-(U2C-RESERVED-Pad81)") (class "Default")
      (node (ref "U2") (pin "81") (pinfunction "RESERVED_81") (pintype "passive+no_connect"))
    )
    (net (code "101") (name "unconnected-(U2C-RESERVED-Pad83)") (class "Default")
      (node (ref "U2") (pin "83") (pinfunction "RESERVED_83") (pintype "passive+no_connect"))
    )
    (net (code "102") (name "unconnected-(U2C-RESERVED-Pad84)") (class "Default")
      (node (ref "U2") (pin "84") (pinfunction "RESERVED_84") (pintype "passive+no_connect"))
    )
    (net (code "103") (name "unconnected-(U2C-RESERVED-Pad85)") (class "Default")
      (node (ref "U2") (pin "85") (pinfunction "RESERVED_85") (pintype "passive+no_connect"))
    )
    (net (code "104") (name "unconnected-(U3-Pad1)") (class "Default")
      (node (ref "U3") (pin "1") (pintype "passive"))
    )
  )
)
